# MotorDriver_Basic.net
KiCad netlist of a schematic drawn in EAGLE
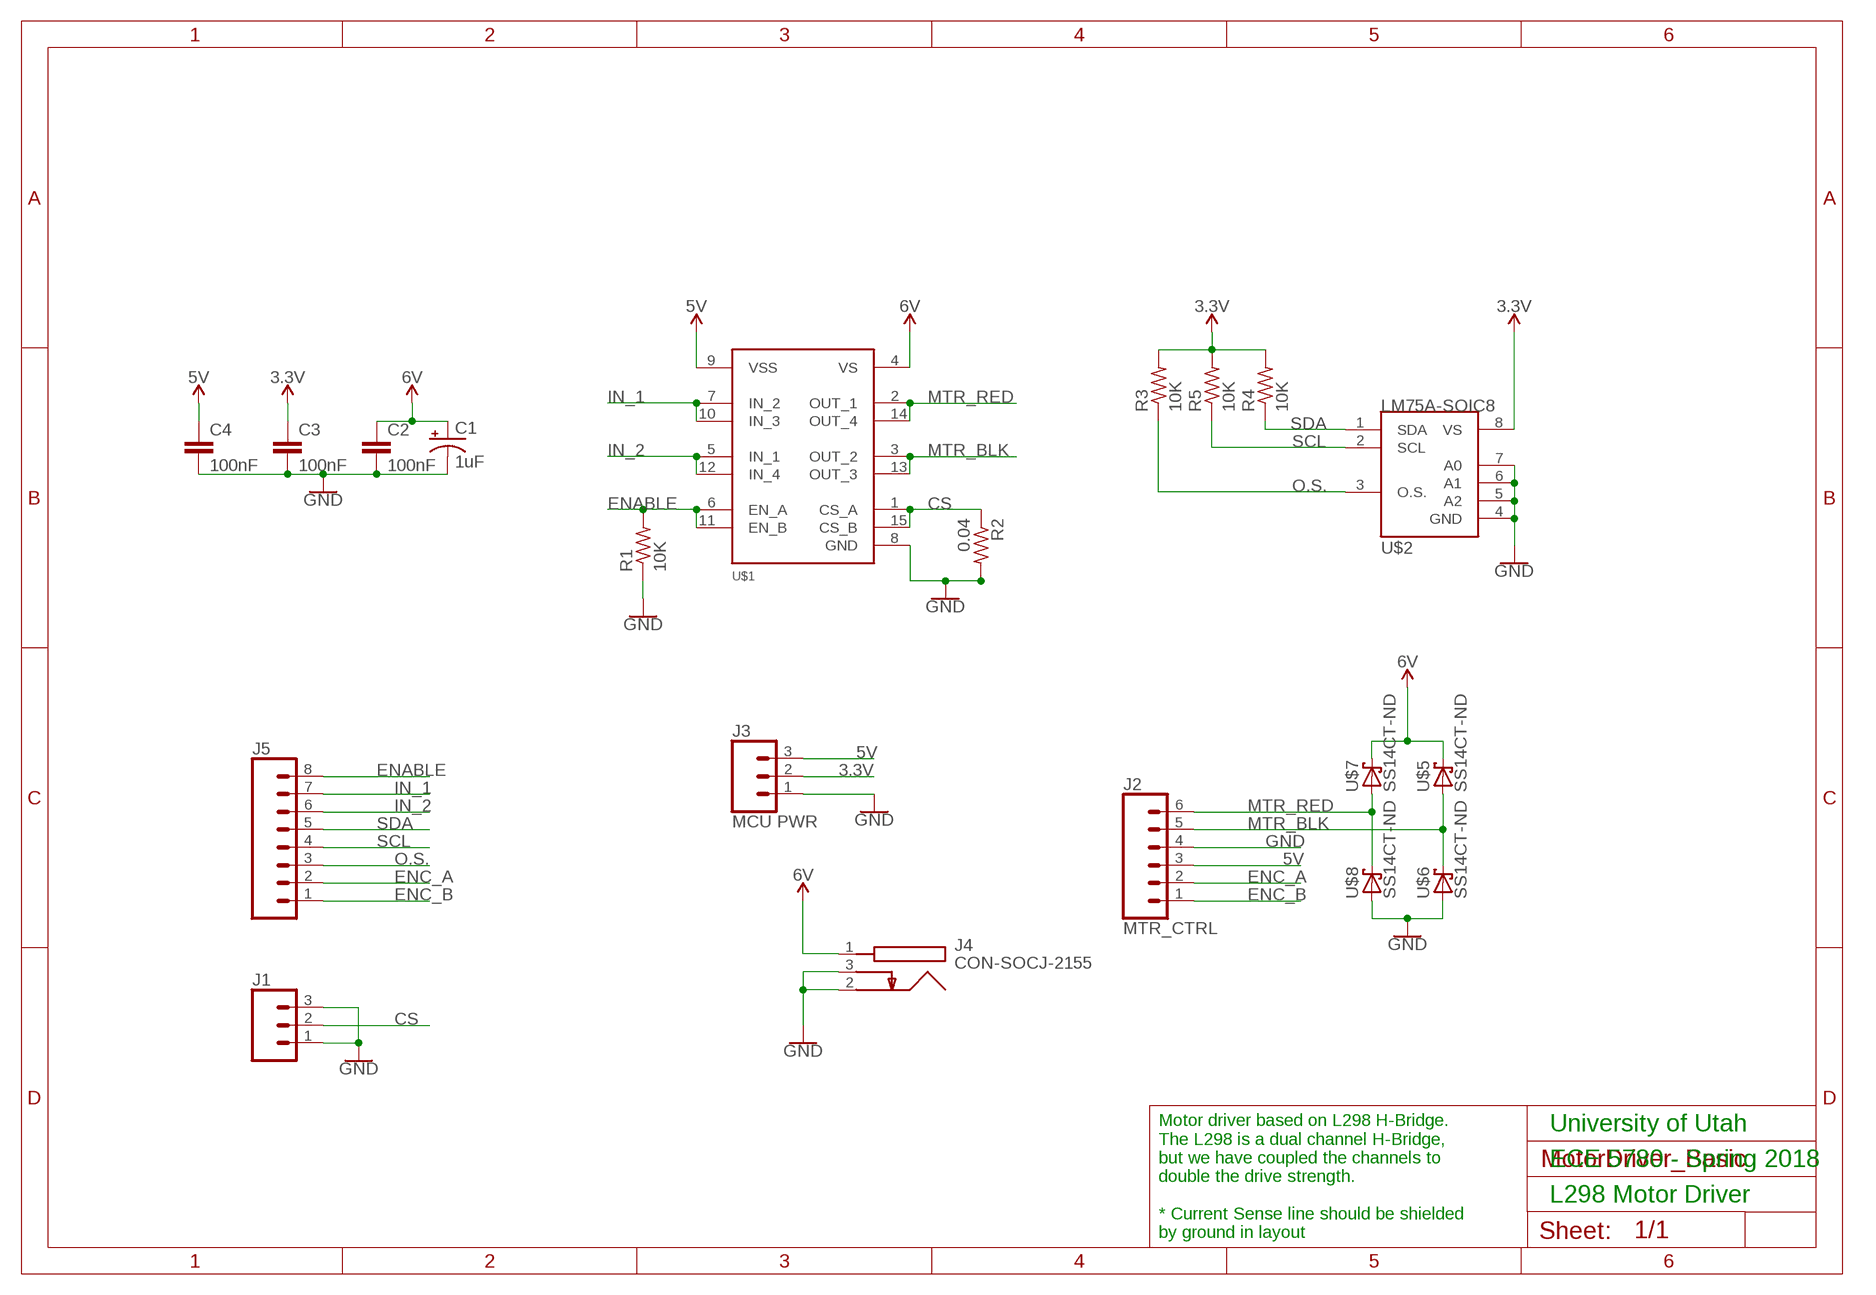
[diagram p0: schematic, sheet 1]

(export (version "E")
  (design (tool "Eeschema 10.0.6"))
  (components
    (comp (ref "C1")
      (value "1uF")
      (footprint "eagle-import:E2,5-6")
      (libsource (lib "eagle-import") (part "CPOL-USE2.5-6"))
    )
    (comp (ref "C2")
      (value "100nF")
      (footprint "eagle-import:C1206")
      (libsource (lib "eagle-import") (part "C-EUC1206"))
    )
    (comp (ref "C3")
      (value "100nF")
      (footprint "eagle-import:C1206")
      (libsource (lib "eagle-import") (part "C-EUC1206"))
    )
    (comp (ref "C4")
      (value "100nF")
      (footprint "eagle-import:C1206")
      (libsource (lib "eagle-import") (part "C-EUC1206"))
    )
    (comp (ref "J1")
      (value "CONN_03")
      (footprint "eagle-import:1X03")
      (libsource (lib "eagle-import") (part "CONN_03"))
    )
    (comp (ref "J2")
      (value "MTR_CTRL")
      (footprint "eagle-import:1X06")
      (libsource (lib "eagle-import") (part "CONN_06SILK_FEMALE_PTH"))
    )
    (comp (ref "J3")
      (value "MCU PWR")
      (footprint "eagle-import:1X03")
      (libsource (lib "eagle-import") (part "CONN_03"))
    )
    (comp (ref "J4")
      (value "CON-SOCJ-2155")
      (footprint "eagle-import:CONSOCJ2155")
      (fields (field (name "MOUSER_PART_NUMBER") "992-CON-SOCJ-2155"))
      (libsource (lib "eagle-import") (part "CON-SOCJ-2155"))
    )
    (comp (ref "J5")
      (value "CONN_08\"")
      (footprint "eagle-import:1X08")
      (libsource (lib "eagle-import") (part "CONN_08{dblquote}"))
    )
    (comp (ref "R1")
      (value "10K")
      (footprint "eagle-import:M1206")
      (libsource (lib "eagle-import") (part "R-US_M1206"))
    )
    (comp (ref "R2")
      (value "0.04")
      (footprint "eagle-import:M1206")
      (libsource (lib "eagle-import") (part "R-US_M1206"))
    )
    (comp (ref "R3")
      (value "10K")
      (footprint "eagle-import:M1206")
      (libsource (lib "eagle-import") (part "R-US_M1206"))
    )
    (comp (ref "R4")
      (value "10K")
      (footprint "eagle-import:M1206")
      (libsource (lib "eagle-import") (part "R-US_M1206"))
    )
    (comp (ref "R5")
      (value "10K")
      (footprint "eagle-import:M1206")
      (libsource (lib "eagle-import") (part "R-US_M1206"))
    )
    (comp (ref "U$1")
      (value "L298N-MULTIWATT15")
      (footprint "eagle-import:L298N-MULTIWATT15")
      (libsource (lib "eagle-import") (part "L298N-MULTIWATT15"))
    )
    (comp (ref "U$2")
      (value "LM75A-SOIC8")
      (footprint "eagle-import:SOIC-8")
      (libsource (lib "eagle-import") (part "LM75A-SOIC8"))
    )
    (comp (ref "U$5")
      (value "SS14CT-ND")
      (footprint "eagle-import:SOD106A-W")
      (libsource (lib "eagle-import") (part "SS14CT-ND"))
    )
    (comp (ref "U$6")
      (value "SS14CT-ND")
      (footprint "eagle-import:SOD106A-W")
      (libsource (lib "eagle-import") (part "SS14CT-ND"))
    )
    (comp (ref "U$7")
      (value "SS14CT-ND")
      (footprint "eagle-import:SOD106A-W")
      (libsource (lib "eagle-import") (part "SS14CT-ND"))
    )
    (comp (ref "U$8")
      (value "SS14CT-ND")
      (footprint "eagle-import:SOD106A-W")
      (libsource (lib "eagle-import") (part "SS14CT-ND"))
    )
  )
  (nets
    (net (code "1") (name "/CS") (class "Default")
      (node (ref "J1") (pin "2") (pinfunction "2_2") (pintype "passive"))
      (node (ref "R2") (pin "1") (pinfunction "1_1") (pintype "passive"))
      (node (ref "U$1") (pin "1") (pinfunction "CS_A_1") (pintype "bidirectional"))
      (node (ref "U$1") (pin "15") (pinfunction "CS_B_15") (pintype "bidirectional"))
    )
    (net (code "2") (name "/ENABLE") (class "Default")
      (node (ref "J5") (pin "8") (pinfunction "8_8") (pintype "passive"))
      (node (ref "R1") (pin "2") (pinfunction "2_2") (pintype "passive"))
      (node (ref "U$1") (pin "11") (pinfunction "EN_B_11") (pintype "bidirectional"))
      (node (ref "U$1") (pin "6") (pinfunction "EN_A_6") (pintype "bidirectional"))
    )
    (net (code "3") (name "/ENC_A") (class "Default")
      (node (ref "J2") (pin "2") (pinfunction "2_2") (pintype "passive"))
      (node (ref "J5") (pin "2") (pinfunction "2_2") (pintype "passive"))
    )
    (net (code "4") (name "/ENC_B") (class "Default")
      (node (ref "J2") (pin "1") (pinfunction "1_1") (pintype "passive"))
      (node (ref "J5") (pin "1") (pinfunction "1_1") (pintype "passive"))
    )
    (net (code "5") (name "/IN_1") (class "Default")
      (node (ref "J5") (pin "7") (pinfunction "7_7") (pintype "passive"))
      (node (ref "U$1") (pin "10") (pinfunction "IN_3_10") (pintype "bidirectional"))
      (node (ref "U$1") (pin "7") (pinfunction "IN_2_7") (pintype "bidirectional"))
    )
    (net (code "6") (name "/IN_2") (class "Default")
      (node (ref "J5") (pin "6") (pinfunction "6_6") (pintype "passive"))
      (node (ref "U$1") (pin "12") (pinfunction "IN_4_12") (pintype "bidirectional"))
      (node (ref "U$1") (pin "5") (pinfunction "IN_1_5") (pintype "bidirectional"))
    )
    (net (code "7") (name "/MTR_BLK") (class "Default")
      (node (ref "J2") (pin "5") (pinfunction "5_5") (pintype "passive"))
      (node (ref "U$1") (pin "13") (pinfunction "OUT_3_13") (pintype "bidirectional"))
      (node (ref "U$1") (pin "3") (pinfunction "OUT_2_3") (pintype "bidirectional"))
      (node (ref "U$5") (pin "A") (pinfunction "A_A") (pintype "passive"))
      (node (ref "U$6") (pin "C") (pinfunction "C_C") (pintype "passive"))
    )
    (net (code "8") (name "/MTR_RED") (class "Default")
      (node (ref "J2") (pin "6") (pinfunction "6_6") (pintype "passive"))
      (node (ref "U$1") (pin "14") (pinfunction "OUT_4_14") (pintype "bidirectional"))
      (node (ref "U$1") (pin "2") (pinfunction "OUT_1_2") (pintype "bidirectional"))
      (node (ref "U$7") (pin "A") (pinfunction "A_A") (pintype "passive"))
      (node (ref "U$8") (pin "C") (pinfunction "C_C") (pintype "passive"))
    )
    (net (code "9") (name "/O.S.") (class "Default")
      (node (ref "J5") (pin "3") (pinfunction "3_3") (pintype "passive"))
      (node (ref "R3") (pin "1") (pinfunction "1_1") (pintype "passive"))
      (node (ref "U$2") (pin "3") (pinfunction "O.S._3") (pintype "bidirectional"))
    )
    (net (code "10") (name "/SCL") (class "Default")
      (node (ref "J5") (pin "4") (pinfunction "4_4") (pintype "passive"))
      (node (ref "R5") (pin "1") (pinfunction "1_1") (pintype "passive"))
      (node (ref "U$2") (pin "2") (pinfunction "SCL_2") (pintype "bidirectional"))
    )
    (net (code "11") (name "/SDA") (class "Default")
      (node (ref "J5") (pin "5") (pinfunction "5_5") (pintype "passive"))
      (node (ref "R4") (pin "1") (pinfunction "1_1") (pintype "passive"))
      (node (ref "U$2") (pin "1") (pinfunction "SDA_1") (pintype "bidirectional"))
    )
    (net (code "12") (name "3.3V") (class "Default")
      (node (ref "C3") (pin "1") (pinfunction "1_1") (pintype "passive"))
      (node (ref "J3") (pin "2") (pinfunction "2_2") (pintype "passive"))
      (node (ref "R3") (pin "2") (pinfunction "2_2") (pintype "passive"))
      (node (ref "R4") (pin "2") (pinfunction "2_2") (pintype "passive"))
      (node (ref "R5") (pin "2") (pinfunction "2_2") (pintype "passive"))
      (node (ref "U$2") (pin "8") (pinfunction "VS_8") (pintype "bidirectional"))
    )
    (net (code "13") (name "5V") (class "Default")
      (node (ref "C4") (pin "1") (pinfunction "1_1") (pintype "passive"))
      (node (ref "J2") (pin "3") (pinfunction "3_3") (pintype "passive"))
      (node (ref "J3") (pin "3") (pinfunction "3_3") (pintype "passive"))
      (node (ref "U$1") (pin "9") (pinfunction "VSS_9") (pintype "bidirectional"))
    )
    (net (code "14") (name "6V") (class "Default")
      (node (ref "C1") (pin "+") (pinfunction "+_+") (pintype "passive"))
      (node (ref "C2") (pin "1") (pinfunction "1_1") (pintype "passive"))
      (node (ref "J4") (pin "1") (pinfunction "1_1") (pintype "bidirectional"))
      (node (ref "U$1") (pin "4") (pinfunction "VS_4") (pintype "bidirectional"))
      (node (ref "U$5") (pin "C") (pinfunction "C_C") (pintype "passive"))
      (node (ref "U$7") (pin "C") (pinfunction "C_C") (pintype "passive"))
    )
    (net (code "15") (name "GND") (class "Default")
      (node (ref "C1") (pin "-") (pinfunction "-_-") (pintype "passive"))
      (node (ref "C2") (pin "2") (pinfunction "2_2") (pintype "passive"))
      (node (ref "C3") (pin "2") (pinfunction "2_2") (pintype "passive"))
      (node (ref "C4") (pin "2") (pinfunction "2_2") (pintype "passive"))
      (node (ref "J1") (pin "1") (pinfunction "1_1") (pintype "passive"))
      (node (ref "J1") (pin "3") (pinfunction "3_3") (pintype "passive"))
      (node (ref "J2") (pin "4") (pinfunction "4_4") (pintype "passive"))
      (node (ref "J3") (pin "1") (pinfunction "1_1") (pintype "passive"))
      (node (ref "J4") (pin "2") (pinfunction "2_2") (pintype "bidirectional"))
      (node (ref "J4") (pin "3") (pinfunction "3_3") (pintype "bidirectional"))
      (node (ref "R1") (pin "1") (pinfunction "1_1") (pintype "passive"))
      (node (ref "R2") (pin "2") (pinfunction "2_2") (pintype "passive"))
      (node (ref "U$1") (pin "8") (pinfunction "GND_8") (pintype "bidirectional"))
      (node (ref "U$2") (pin "4") (pinfunction "GND_4") (pintype "bidirectional"))
      (node (ref "U$2") (pin "5") (pinfunction "A2_5") (pintype "bidirectional"))
      (node (ref "U$2") (pin "6") (pinfunction "A1_6") (pintype "bidirectional"))
      (node (ref "U$2") (pin "7") (pinfunction "A0_7") (pintype "bidirectional"))
      (node (ref "U$6") (pin "A") (pinfunction "A_A") (pintype "passive"))
      (node (ref "U$8") (pin "A") (pinfunction "A_A") (pintype "passive"))
    )
  )
)
